# example.net
KiCad netlist of a schematic drawn in EAGLE
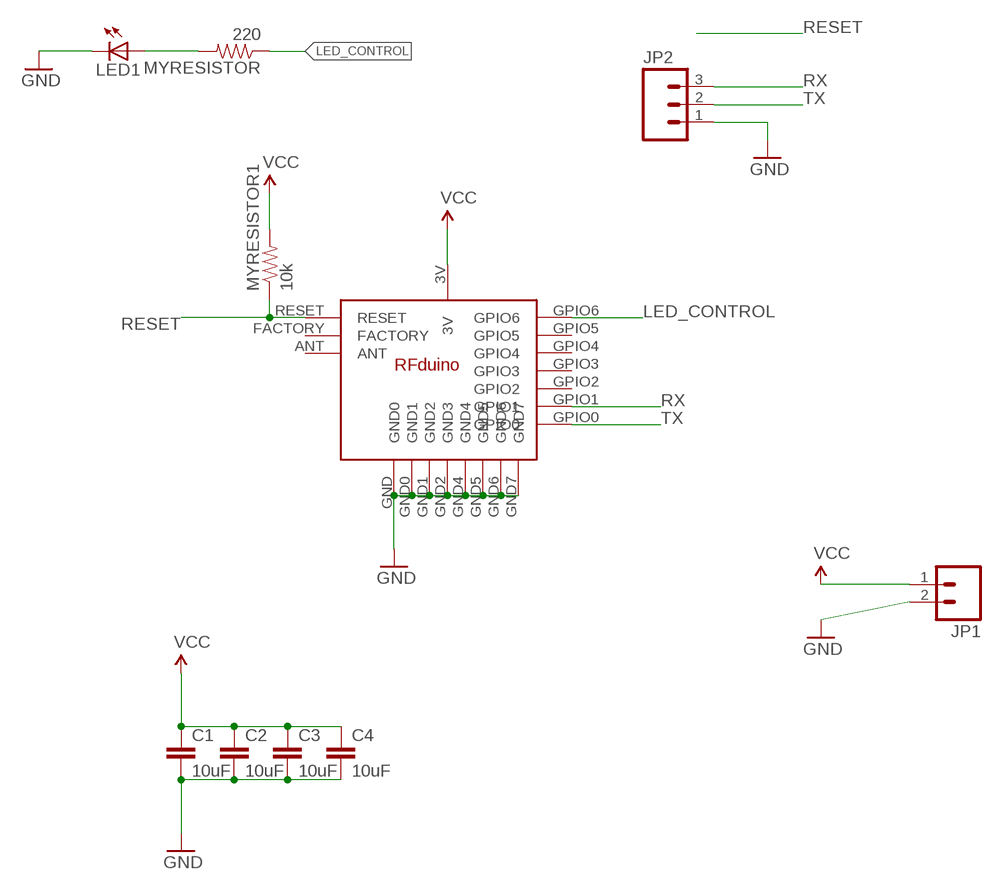
[diagram p0: schematic, sheet 1]

(export (version "E")
  (design (tool "Eeschema 10.0.6"))
  (components
    (comp (ref "C1")
      (value "10uF")
      (footprint "eagle-import:0603-CAP")
      (libsource (lib "eagle-import") (part "CAP0603-CAP"))
    )
    (comp (ref "C2")
      (value "10uF")
      (footprint "eagle-import:0603-CAP")
      (libsource (lib "eagle-import") (part "CAP0603-CAP"))
    )
    (comp (ref "C3")
      (value "10uF")
      (footprint "eagle-import:0603-CAP")
      (libsource (lib "eagle-import") (part "CAP0603-CAP"))
    )
    (comp (ref "C4")
      (value "10uF")
      (footprint "eagle-import:0603-CAP")
      (libsource (lib "eagle-import") (part "CAP0603-CAP"))
    )
    (comp (ref "JP1")
      (value "M02")
      (footprint "eagle-import:1X02_LONGPADS")
      (libsource (lib "eagle-import") (part "M02"))
    )
    (comp (ref "JP2")
      (value "M03PTH")
      (footprint "eagle-import:1X03")
      (libsource (lib "eagle-import") (part "M03PTH"))
    )
    (comp (ref "LED1")
      (value "LEDCHIP-LED0603")
      (footprint "eagle-import:CHIP-LED0603")
      (libsource (lib "eagle-import") (part "LEDCHIP-LED0603"))
    )
    (comp (ref "MYRESISTOR")
      (value "220")
      (footprint "eagle-import:0603-RES")
      (libsource (lib "eagle-import") (part "RESISTOR0603-RES"))
    )
    (comp (ref "MYRESISTOR1")
      (value "10k")
      (footprint "eagle-import:0603-RES")
      (libsource (lib "eagle-import") (part "RESISTOR0603-RES"))
    )
    (comp (ref "U$2")
      (value "RFDUINO")
      (footprint "eagle-import:RFDUINO")
      (libsource (lib "eagle-import") (part "RFDUINO"))
    )
  )
  (nets
    (net (code "1") (name "/RESET") (class "Default")
      (node (ref "MYRESISTOR1") (pin "1") (pinfunction "1_1") (pintype "passive"))
      (node (ref "U$2") (pin "RESET") (pinfunction "RESET_RESET") (pintype "bidirectional"))
    )
    (net (code "2") (name "/RX") (class "Default")
      (node (ref "JP2") (pin "3") (pinfunction "3_3") (pintype "passive"))
      (node (ref "U$2") (pin "GPIO1") (pinfunction "GPIO1_GPIO1") (pintype "bidirectional"))
    )
    (net (code "3") (name "/TX") (class "Default")
      (node (ref "JP2") (pin "2") (pinfunction "2_2") (pintype "passive"))
      (node (ref "U$2") (pin "GPIO0") (pinfunction "GPIO0_GPIO0") (pintype "bidirectional"))
    )
    (net (code "4") (name "GND") (class "Default")
      (node (ref "C1") (pin "2") (pinfunction "2_2") (pintype "passive"))
      (node (ref "C2") (pin "2") (pinfunction "2_2") (pintype "passive"))
      (node (ref "C3") (pin "2") (pinfunction "2_2") (pintype "passive"))
      (node (ref "C4") (pin "2") (pinfunction "2_2") (pintype "passive"))
      (node (ref "JP1") (pin "2") (pinfunction "2_2") (pintype "passive"))
      (node (ref "JP2") (pin "1") (pinfunction "1_1") (pintype "passive"))
      (node (ref "LED1") (pin "C") (pinfunction "C_C") (pintype "passive"))
      (node (ref "U$2") (pin "GND") (pinfunction "GND0_GND") (pintype "bidirectional"))
      (node (ref "U$2") (pin "GND0") (pinfunction "GND1_GND0") (pintype "bidirectional"))
      (node (ref "U$2") (pin "GND1") (pinfunction "GND2_GND1") (pintype "bidirectional"))
      (node (ref "U$2") (pin "GND2") (pinfunction "GND3_GND2") (pintype "bidirectional"))
      (node (ref "U$2") (pin "GND4") (pinfunction "GND4_GND4") (pintype "bidirectional"))
      (node (ref "U$2") (pin "GND5") (pinfunction "GND5_GND5") (pintype "bidirectional"))
      (node (ref "U$2") (pin "GND6") (pinfunction "GND6_GND6") (pintype "bidirectional"))
      (node (ref "U$2") (pin "GND7") (pinfunction "GND7_GND7") (pintype "bidirectional"))
    )
    (net (code "5") (name "LED_CONTROL") (class "Default")
      (node (ref "MYRESISTOR") (pin "1") (pinfunction "1_1") (pintype "passive"))
      (node (ref "U$2") (pin "GPIO6") (pinfunction "GPIO6_GPIO6") (pintype "bidirectional"))
    )
    (net (code "6") (name "Net-(LED1-PadA)") (class "Default")
      (node (ref "LED1") (pin "A") (pinfunction "A_A") (pintype "passive"))
      (node (ref "MYRESISTOR") (pin "2") (pinfunction "2_2") (pintype "passive"))
    )
    (net (code "7") (name "VCC") (class "Default")
      (node (ref "C1") (pin "1") (pinfunction "1_1") (pintype "passive"))
      (node (ref "C2") (pin "1") (pinfunction "1_1") (pintype "passive"))
      (node (ref "C3") (pin "1") (pinfunction "1_1") (pintype "passive"))
      (node (ref "C4") (pin "1") (pinfunction "1_1") (pintype "passive"))
      (node (ref "JP1") (pin "1") (pinfunction "1_1") (pintype "passive"))
      (node (ref "MYRESISTOR1") (pin "2") (pinfunction "2_2") (pintype "passive"))
      (node (ref "U$2") (pin "3V") (pinfunction "3V_3V") (pintype "bidirectional"))
    )
    (net (code "8") (name "unconnected-(U$2-PadANT)") (class "Default")
      (node (ref "U$2") (pin "ANT") (pinfunction "ANT_ANT") (pintype "bidirectional"))
    )
    (net (code "9") (name "unconnected-(U$2-PadFACTORY)") (class "Default")
      (node (ref "U$2") (pin "FACTORY") (pinfunction "FACTORY_FACTORY") (pintype "bidirectional"))
    )
    (net (code "10") (name "unconnected-(U$2-PadGPIO2)") (class "Default")
      (node (ref "U$2") (pin "GPIO2") (pinfunction "GPIO2_GPIO2") (pintype "bidirectional"))
    )
    (net (code "11") (name "unconnected-(U$2-PadGPIO3)") (class "Default")
      (node (ref "U$2") (pin "GPIO3") (pinfunction "GPIO3_GPIO3") (pintype "bidirectional"))
    )
    (net (code "12") (name "unconnected-(U$2-PadGPIO4)") (class "Default")
      (node (ref "U$2") (pin "GPIO4") (pinfunction "GPIO4_GPIO4") (pintype "bidirectional"))
    )
    (net (code "13") (name "unconnected-(U$2-PadGPIO5)") (class "Default")
      (node (ref "U$2") (pin "GPIO5") (pinfunction "GPIO5_GPIO5") (pintype "bidirectional"))
    )
  )
)
